# logger_sensors.net
KiCad netlist of a schematic drawn in Altium Designer
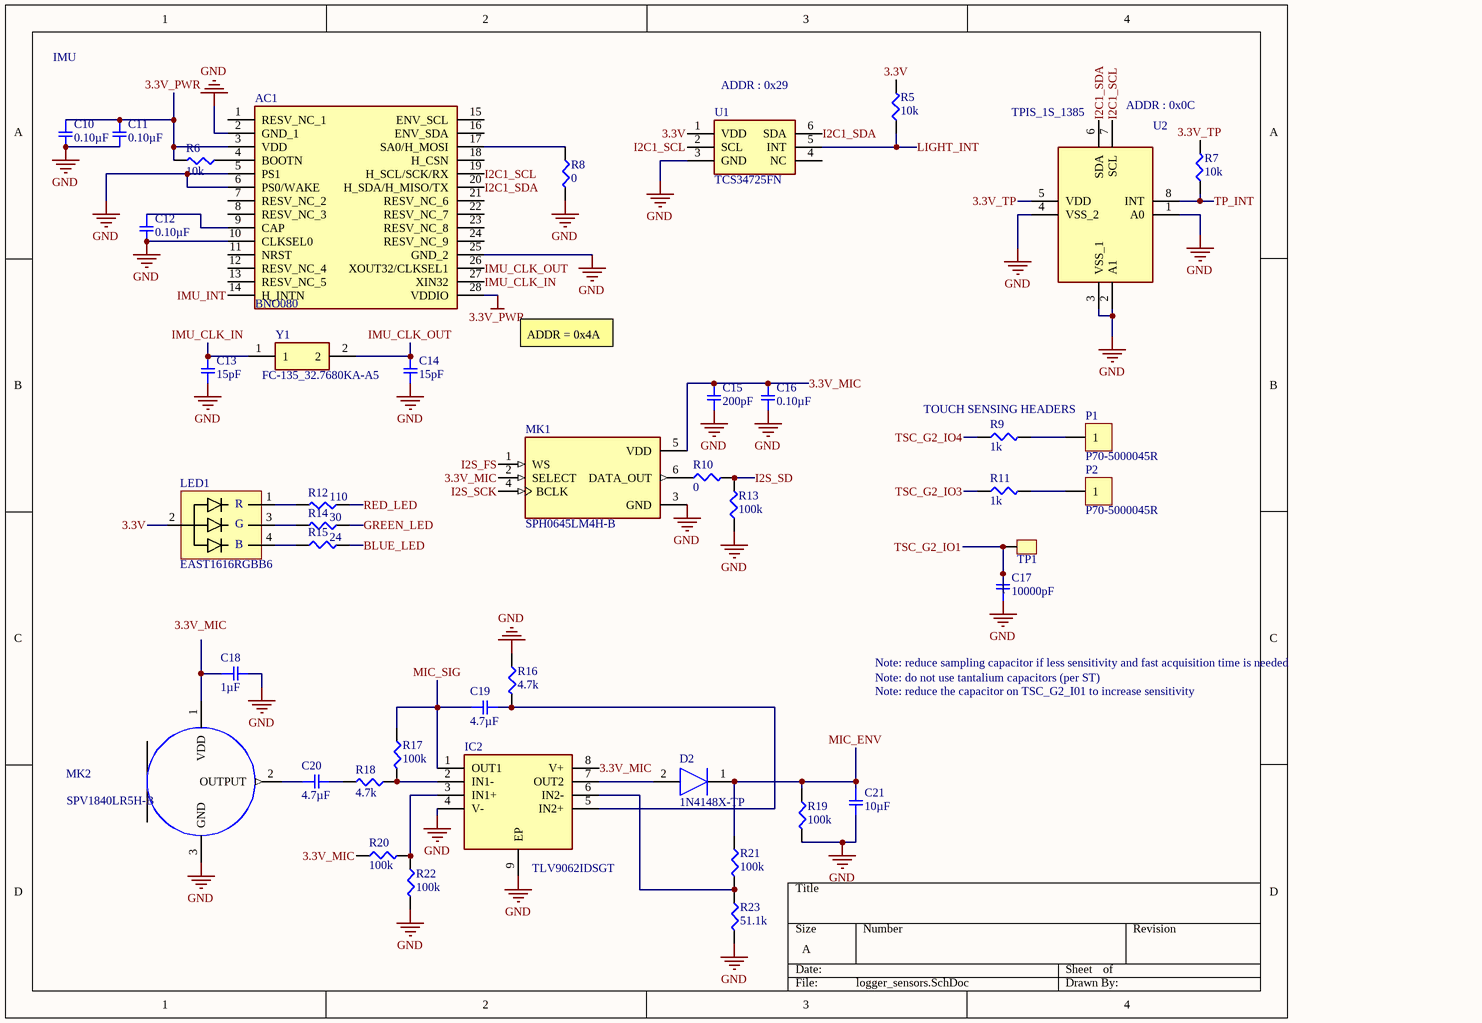
[diagram p0: logger_sensors.SchDoc]

(export (version "E")
  (design (tool "Eeschema 10.0.6"))
  (components
    (comp (ref "AC1")
      (value "BNO080")
      (footprint "BNO080")
      (description "Accelerometer")
      (libsource (lib "*") (part "BNO080"))
    )
    (comp (ref "C10")
      (value "0.10µF")
      (footprint "CAPC1005X55N")
      (description "CAP CER 0.1UF 16V X7R 0402")
      (fields
        (field (name "DIGI-KEY PART NUMBER") "490-4759-1-ND")
        (field (name "PART NUMBER") "GCM155R71C104KA55D")
      )
      (libsource (lib "capacitor_murata_0402") (part "GCM155R71C104KA55D"))
    )
    (comp (ref "C11")
      (value "0.10µF")
      (footprint "CAPC1005X55N")
      (description "CAP CER 0.1UF 16V X7R 0402")
      (fields
        (field (name "DIGI-KEY PART NUMBER") "490-4759-1-ND")
        (field (name "PART NUMBER") "GCM155R71C104KA55D")
      )
      (libsource (lib "capacitor_murata_0402") (part "GCM155R71C104KA55D"))
    )
    (comp (ref "C12")
      (value "0.10µF")
      (footprint "CAPC1005X55N")
      (description "CAP CER 0.1UF 16V X7R 0402")
      (fields
        (field (name "DIGI-KEY PART NUMBER") "490-4759-1-ND")
        (field (name "PART NUMBER") "GCM155R71C104KA55D")
      )
      (libsource (lib "capacitor_murata_0402") (part "GCM155R71C104KA55D"))
    )
    (comp (ref "C13")
      (value "15pF")
      (footprint "CAPC1005X55N")
      (description "CAP CER 15PF 50V NP0 0402")
      (fields
        (field (name "DIGI-KEY PART NUMBER") "490-11147-1-ND")
        (field (name "PART NUMBER") "GCM1555C1H150JA16D")
      )
      (libsource (lib "capacitor_murata_0402") (part "GCM1555C1H150JA16D"))
    )
    (comp (ref "C14")
      (value "15pF")
      (footprint "CAPC1005X55N")
      (description "CAP CER 15PF 50V NP0 0402")
      (fields
        (field (name "DIGI-KEY PART NUMBER") "490-11147-1-ND")
        (field (name "PART NUMBER") "GCM1555C1H150JA16D")
      )
      (libsource (lib "capacitor_murata_0402") (part "GCM1555C1H150JA16D"))
    )
    (comp (ref "C15")
      (value "200pF")
      (footprint "CAPC1005X55N")
      (description "CAP CER 200pF 16V X7R 0402")
      (fields
        (field (name "DIGI-KEY PART NUMBER") "490-4759-1-ND")
        (field (name "PART NUMBER") "GCM155R71C104KA55D")
      )
      (libsource (lib "capacitor_murata_0402") (part "GCM155R71C104KA55D"))
    )
    (comp (ref "C16")
      (value "0.10µF")
      (footprint "CAPC1005X55N")
      (description "CAP CER 0.1UF 16V X7R 0402")
      (fields
        (field (name "DIGI-KEY PART NUMBER") "490-4759-1-ND")
        (field (name "PART NUMBER") "GCM155R71C104KA55D")
      )
      (libsource (lib "capacitor_murata_0402") (part "GCM155R71C104KA55D"))
    )
    (comp (ref "C17")
      (value "10000pF")
      (footprint "SMD-0402C")
      (description "CAP CER 10000PF 50V X7R 0402")
      (fields
        (field (name "DIGI-KEY PART NUMBER") "490-4762-1-ND")
        (field (name "PART NUMBER") "GCM155R71H103KA55D")
      )
      (libsource (lib "capacitor_murata_0402") (part "GCM155R71H103KA55D"))
    )
    (comp (ref "C18")
      (value "1µF")
      (footprint "SMD-0402C")
      (description "CAP CER 1UF 10V X7S 0402")
      (fields
        (field (name "DIGI-KEY PART NUMBER") "490-13409-1-ND")
        (field (name "PART NUMBER") "GCM155C71A105KE38D")
      )
      (libsource (lib "capacitor_murata_0402") (part "GCM155C71A105KE38D"))
    )
    (comp (ref "C19")
      (value "4.7µF")
      (footprint "SMD-0402C")
      (description "CAP CER 4.7UF 6.3V X5R 0402")
      (fields
        (field (name "DIGI-KEY PART NUMBER") "490-5915-1-ND")
        (field (name "PART NUMBER") "GRM155R60J475ME47D")
      )
      (libsource (lib "capacitor_murata_0402") (part "GRM155R60J475ME47D"))
    )
    (comp (ref "C20")
      (value "4.7µF")
      (footprint "SMD-0402C")
      (description "CAP CER 4.7UF 6.3V X5R 0402")
      (fields
        (field (name "DIGI-KEY PART NUMBER") "490-5915-1-ND")
        (field (name "PART NUMBER") "GRM155R60J475ME47D")
      )
      (libsource (lib "capacitor_murata_0402") (part "GRM155R60J475ME47D"))
    )
    (comp (ref "C21")
      (value "10µF")
      (footprint "CAPC1005X55N")
      (description "CAP CER 10UF 16V X7R 0402")
      (fields
        (field (name "DIGI-KEY PART NUMBER") "490-4759-1-ND")
        (field (name "PART NUMBER") "GCM155R71C104KA55D")
      )
      (libsource (lib "capacitor_murata_0402") (part "GCM155R71C104KA55D"))
    )
    (comp (ref "D2")
      (value "1N4148X-TP")
      (footprint "SamacSys:SODFL1608X70N")
      (description "Diode")
      (fields (field (name "MOUSER PART NUMBER") "833-1N4148X-TP"))
      (libsource (lib "*") (part "1N4148X-TP"))
    )
    (comp (ref "IC2")
      (value "TLV9062IDSGT")
      (footprint "SON50P200X200X80-9N")
      (description "Integrated Circuit")
      (fields (field (name "MOUSER PART NUMBER") "595-TLV9062IDSGT"))
      (libsource (lib "SamacSys") (part "TLV9062IDSGT"))
    )
    (comp (ref "LED1")
      (value "EAST1616RGBB6")
      (footprint "EAST1616RGBB6")
      (libsource (lib "schematic_components") (part "EAST1616RGBB6"))
    )
    (comp (ref "MK1")
      (value "SPH0645LM4H-B")
      (footprint "MIC_SPH0645LM4H-B")
      (fields (field (name "DIGI-KEY_PART_NUMBER") "423-1405-1-ND") (field (name "MF") "Knowles"))
      (libsource (lib "schematic_components") (part "SPH0645LM4H-B"))
    )
    (comp (ref "MK2")
      (value "SPV1840LR5H-B")
      (footprint "*MIC_SPV1840LR5H-B")
      (description "Mic Mems Analog")
      (fields (field (name "MF") "Knowles"))
      (libsource (lib "schematic_components") (part "SPV1840LR5H-B"))
    )
    (comp (ref "P1")
      (value "P70-5000045R")
      (footprint "P70-5000045R")
      (libsource (lib "schematic_components") (part "P70-5000045R"))
    )
    (comp (ref "P2")
      (value "P70-5000045R")
      (footprint "P70-5000045R")
      (libsource (lib "schematic_components") (part "P70-5000045R"))
    )
    (comp (ref "R5")
      (value "10k")
      (footprint "SMD-0402-RES")
      (description "RES SMD 10K OHM 5% 1/10W 0402")
      (fields (field (name "PART NUMBER") "ERJ-2GEJ103X") (field (name "DIGI-KEY PART NUMBER") "P10KJCT-ND"))
      (libsource (lib "Panasonic_ERJ_0402") (part "ERJ-2GEJ103X"))
    )
    (comp (ref "R6")
      (value "10k")
      (footprint "SMD-0402-RES")
      (description "RES SMD 10K OHM 5% 1/10W 0402")
      (fields (field (name "PART NUMBER") "ERJ-2GEJ103X") (field (name "DIGI-KEY PART NUMBER") "P10KJCT-ND"))
      (libsource (lib "Panasonic_ERJ_0402") (part "ERJ-2GEJ103X"))
    )
    (comp (ref "R7")
      (value "10k")
      (footprint "SMD-0402-RES")
      (description "RES SMD 10K OHM 5% 1/10W 0402")
      (fields (field (name "PART NUMBER") "ERJ-2GEJ103X") (field (name "DIGI-KEY PART NUMBER") "P10KJCT-ND"))
      (libsource (lib "Panasonic_ERJ_0402") (part "ERJ-2GEJ103X"))
    )
    (comp (ref "R8")
      (value "0")
      (footprint "SMD-0402-RES")
      (description "RES SMD 0K OHM 5% 1/10W 0402")
      (fields (field (name "PART NUMBER") "ERJ-2GEJ103X") (field (name "DIGI-KEY PART NUMBER") "P10KJCT-ND"))
      (libsource (lib "Panasonic_ERJ_0402") (part "ERJ-2GEJ103X"))
    )
    (comp (ref "R9")
      (value "1k")
      (footprint "SMD-0402-RES")
      (description "RES SMD 1K OHM 5% 1/10W 0402")
      (fields (field (name "PART NUMBER") "ERJ-2GEJ102X") (field (name "DIGI-KEY PART NUMBER") "P1.0KJCT-ND"))
      (libsource (lib "Panasonic_ERJ_0402") (part "ERJ-2GEJ102X"))
    )
    (comp (ref "R10")
      (value "0")
      (footprint "SMD-0402-RES")
      (description "RES SMD 0K OHM 5% 1/10W 0402")
      (fields (field (name "PART NUMBER") "ERJ-2GEJ103X") (field (name "DIGI-KEY PART NUMBER") "P10KJCT-ND"))
      (libsource (lib "Panasonic_ERJ_0402") (part "ERJ-2GEJ103X"))
    )
    (comp (ref "R11")
      (value "1k")
      (footprint "SMD-0402-RES")
      (description "RES SMD 1K OHM 5% 1/10W 0402")
      (fields (field (name "PART NUMBER") "ERJ-2GEJ102X") (field (name "DIGI-KEY PART NUMBER") "P1.0KJCT-ND"))
      (libsource (lib "Panasonic_ERJ_0402") (part "ERJ-2GEJ102X"))
    )
    (comp (ref "R12")
      (value "110")
      (footprint "SMD-0402-RES")
      (description "RES SMD 110 OHM 5% 1/10W 0402")
      (fields (field (name "PART NUMBER") "ERJ-2GEJ103X") (field (name "DIGI-KEY PART NUMBER") "P10KJCT-ND"))
      (libsource (lib "Panasonic_ERJ_0402") (part "ERJ-2GEJ103X"))
    )
    (comp (ref "R13")
      (value "100k")
      (footprint "SMD-0402-RES")
      (description "RES SMD 100K OHM 5% 1/10W 0402")
      (fields (field (name "PART NUMBER") "ERJ-2GEJ103X") (field (name "DIGI-KEY PART NUMBER") "P10KJCT-ND"))
      (libsource (lib "Panasonic_ERJ_0402") (part "ERJ-2GEJ103X"))
    )
    (comp (ref "R14")
      (value "30")
      (footprint "SMD-0402-RES")
      (description "RES SMD 110 OHM 5% 1/10W 0402")
      (fields (field (name "PART NUMBER") "ERJ-2GEJ103X") (field (name "DIGI-KEY PART NUMBER") "P10KJCT-ND"))
      (libsource (lib "Panasonic_ERJ_0402") (part "ERJ-2GEJ103X"))
    )
    (comp (ref "R15")
      (value "24")
      (footprint "SMD-0402-RES")
      (description "RES SMD 110 OHM 5% 1/10W 0402")
      (fields (field (name "PART NUMBER") "ERJ-2GEJ103X") (field (name "DIGI-KEY PART NUMBER") "P10KJCT-ND"))
      (libsource (lib "Panasonic_ERJ_0402") (part "ERJ-2GEJ103X"))
    )
    (comp (ref "R16")
      (value "4.7k")
      (footprint "SMD-0402-RES")
      (description "RES SMD 4.7K OHM 5% 1/10W 0402")
      (fields (field (name "PART NUMBER") "ERJ-2GEJ103X") (field (name "DIGI-KEY PART NUMBER") "P10KJCT-ND"))
      (libsource (lib "Panasonic_ERJ_0402") (part "ERJ-2GEJ103X"))
    )
    (comp (ref "R17")
      (value "100k")
      (footprint "SMD-0402-RES")
      (description "RES SMD 100K OHM 5% 1/10W 0402")
      (fields (field (name "PART NUMBER") "ERJ-2GEJ103X") (field (name "DIGI-KEY PART NUMBER") "P10KJCT-ND"))
      (libsource (lib "Panasonic_ERJ_0402") (part "ERJ-2GEJ103X"))
    )
    (comp (ref "R18")
      (value "4.7k")
      (footprint "SMD-0402-RES")
      (description "RES SMD 4.7K OHM 5% 1/10W 0402")
      (fields (field (name "PART NUMBER") "ERJ-2GEJ103X") (field (name "DIGI-KEY PART NUMBER") "P10KJCT-ND"))
      (libsource (lib "Panasonic_ERJ_0402") (part "ERJ-2GEJ103X"))
    )
    (comp (ref "R19")
      (value "100k")
      (footprint "SMD-0402-RES")
      (description "RES SMD 100K OHM 5% 1/10W 0402")
      (fields (field (name "PART NUMBER") "ERJ-2GEJ103X") (field (name "DIGI-KEY PART NUMBER") "P10KJCT-ND"))
      (libsource (lib "Panasonic_ERJ_0402") (part "ERJ-2GEJ103X"))
    )
    (comp (ref "R20")
      (value "100k")
      (footprint "SMD-0402-RES")
      (description "RES SMD 100K OHM 5% 1/10W 0402")
      (fields (field (name "PART NUMBER") "ERJ-2GEJ103X") (field (name "DIGI-KEY PART NUMBER") "P10KJCT-ND"))
      (libsource (lib "Panasonic_ERJ_0402") (part "ERJ-2GEJ103X"))
    )
    (comp (ref "R21")
      (value "100k")
      (footprint "SMD-0402-RES")
      (description "RES SMD 100K OHM 5% 1/10W 0402")
      (fields (field (name "PART NUMBER") "ERJ-2GEJ103X") (field (name "DIGI-KEY PART NUMBER") "P10KJCT-ND"))
      (libsource (lib "Panasonic_ERJ_0402") (part "ERJ-2GEJ103X"))
    )
    (comp (ref "R22")
      (value "100k")
      (footprint "SMD-0402-RES")
      (description "RES SMD 100K OHM 5% 1/10W 0402")
      (fields (field (name "PART NUMBER") "ERJ-2GEJ103X") (field (name "DIGI-KEY PART NUMBER") "P10KJCT-ND"))
      (libsource (lib "Panasonic_ERJ_0402") (part "ERJ-2GEJ103X"))
    )
    (comp (ref "R23")
      (value "51.1k")
      (footprint "SMD-0402-RES")
      (description "RES SMD 51.1K OHM 5% 1/10W 0402")
      (fields (field (name "PART NUMBER") "ERJ-2GEJ103X") (field (name "DIGI-KEY PART NUMBER") "P10KJCT-ND"))
      (libsource (lib "Panasonic_ERJ_0402") (part "ERJ-2GEJ103X"))
    )
    (comp (ref "TP1")
      (value "TestPoint")
      (footprint "TestPoint_0.4mm")
      (libsource (lib "schematic_components") (part "TestPoint"))
    )
    (comp (ref "U1")
      (value "TCS34725FN")
      (footprint "SamacSys:FN_1")
      (description "Undefined or Miscellaneous")
      (fields (field (name "MOUSER PART NUMBER") "985-TCS34725FN") (field (name "RS PART NUMBER") "1024173P"))
      (libsource (lib "*") (part "TCS34725FN"))
    )
    (comp (ref "U2")
      (value "TPIS_1S_1385")
      (footprint "SamacSys:TPIS_1S_1385")
      (description "Undefined or Miscellaneous")
      (fields (field (name "MANUFACTURER_PART_NUMBER") "TPIS 1S 1385"))
      (libsource (lib "*") (part "TPIS_1S_1385"))
    )
    (comp (ref "Y1")
      (value "FC-135_32.7680KA-A5")
      (footprint "FC135327680KAAG0")
      (description "Crystal or Oscillator")
      (fields
        (field (name "MANUFACTURER_PART_NUMBER") "FC-135 32.7680KA-A5")
        (field (name "MOUSER PART NUMBER") "732-FC135-32.76KAA3")
      )
      (libsource (lib "*") (part "FC-135_32.7680KA-A3"))
    )
  )
  (nets
    (net (code "1") (name "/3.3V") (class "Default")
      (node (ref "LED1") (pin "2") (pinfunction "2_2") (pintype "passive"))
      (node (ref "R5") (pin "2") (pinfunction "2_2") (pintype "passive"))
      (node (ref "U1") (pin "1") (pinfunction "VDD_1") (pintype "passive"))
    )
    (net (code "2") (name "/3.3V_MIC") (class "Default")
      (node (ref "C15") (pin "1") (pinfunction "1_1") (pintype "passive"))
      (node (ref "C16") (pin "1") (pinfunction "1_1") (pintype "passive"))
      (node (ref "IC2") (pin "8") (pinfunction "V+_8") (pintype "passive"))
      (node (ref "MK1") (pin "2") (pinfunction "SELECT_2") (pintype "input"))
      (node (ref "MK1") (pin "5") (pinfunction "VDD_5") (pintype "power_in"))
      (node (ref "R20") (pin "1") (pinfunction "1_1") (pintype "passive"))
    )
    (net (code "3") (name "/3.3V_TP") (class "Default")
      (node (ref "R7") (pin "2") (pinfunction "2_2") (pintype "passive"))
      (node (ref "U2") (pin "5") (pinfunction "VDD_5") (pintype "passive"))
    )
    (net (code "4") (name "/BLUE_LED") (class "Default")
      (node (ref "R15") (pin "2") (pinfunction "2_2") (pintype "passive"))
    )
    (net (code "5") (name "/GREEN_LED") (class "Default")
      (node (ref "R14") (pin "1") (pinfunction "1_1") (pintype "passive"))
    )
    (net (code "6") (name "/I2C1_SCL") (class "Default")
      (node (ref "AC1") (pin "19") (pinfunction "H_SCL/SCK/RX_19") (pintype "passive"))
      (node (ref "U1") (pin "2") (pinfunction "SCL_2") (pintype "passive"))
      (node (ref "U2") (pin "7") (pinfunction "SCL_7") (pintype "passive"))
    )
    (net (code "7") (name "/I2C1_SDA") (class "Default")
      (node (ref "AC1") (pin "20") (pinfunction "H_SDA/H_MISO/TX_20") (pintype "passive"))
      (node (ref "U1") (pin "6") (pinfunction "SDA_6") (pintype "passive"))
      (node (ref "U2") (pin "6") (pinfunction "SDA_6") (pintype "passive"))
    )
    (net (code "8") (name "/I2S_FS") (class "Default")
      (node (ref "MK1") (pin "1") (pinfunction "WS_1") (pintype "input"))
    )
    (net (code "9") (name "/I2S_SCK") (class "Default")
      (node (ref "MK1") (pin "4") (pinfunction "BCLK_4") (pintype "input"))
    )
    (net (code "10") (name "/I2S_SD") (class "Default")
      (node (ref "R10") (pin "2") (pinfunction "2_2") (pintype "passive"))
      (node (ref "R13") (pin "2") (pinfunction "2_2") (pintype "passive"))
    )
    (net (code "11") (name "/IMU_CLK_IN") (class "Default")
      (node (ref "AC1") (pin "27") (pinfunction "XIN32_27") (pintype "passive"))
      (node (ref "C13") (pin "1") (pinfunction "1_1") (pintype "passive"))
      (node (ref "Y1") (pin "1") (pinfunction "1_1") (pintype "passive"))
    )
    (net (code "12") (name "/IMU_CLK_OUT") (class "Default")
      (node (ref "AC1") (pin "26") (pinfunction "XOUT32/CLKSEL1_26") (pintype "passive"))
      (node (ref "C14") (pin "1") (pinfunction "1_1") (pintype "passive"))
      (node (ref "Y1") (pin "2") (pinfunction "2_2") (pintype "passive"))
    )
    (net (code "13") (name "/IMU_INT") (class "Default")
      (node (ref "AC1") (pin "14") (pinfunction "H_INTN_14") (pintype "passive"))
    )
    (net (code "14") (name "/LIGHT_INT") (class "Default")
      (node (ref "R5") (pin "1") (pinfunction "1_1") (pintype "passive"))
      (node (ref "U1") (pin "5") (pinfunction "INT_5") (pintype "passive"))
    )
    (net (code "15") (name "/MIC_ENV") (class "Default")
      (node (ref "C21") (pin "1") (pinfunction "1_1") (pintype "passive"))
      (node (ref "D2") (pin "1") (pinfunction "K_1") (pintype "passive"))
      (node (ref "R19") (pin "1") (pinfunction "1_1") (pintype "passive"))
      (node (ref "R21") (pin "1") (pinfunction "1_1") (pintype "passive"))
    )
    (net (code "16") (name "/MIC_SIG") (class "Default")
      (node (ref "C19") (pin "1") (pinfunction "1_1") (pintype "passive"))
      (node (ref "IC2") (pin "1") (pinfunction "OUT1_1") (pintype "passive"))
      (node (ref "R17") (pin "1") (pinfunction "1_1") (pintype "passive"))
    )
    (net (code "17") (name "/RED_LED") (class "Default")
      (node (ref "R12") (pin "1") (pinfunction "1_1") (pintype "passive"))
    )
    (net (code "18") (name "/TP_INT") (class "Default")
      (node (ref "R7") (pin "1") (pinfunction "1_1") (pintype "passive"))
      (node (ref "U2") (pin "8") (pinfunction "INT_8") (pintype "passive"))
    )
    (net (code "19") (name "/TSC_G2_IO1") (class "Default")
      (node (ref "C17") (pin "2") (pinfunction "2_2") (pintype "passive"))
      (node (ref "TP1") (pin "1") (pinfunction "1_1") (pintype "passive"))
    )
    (net (code "20") (name "/TSC_G2_IO3") (class "Default")
      (node (ref "R11") (pin "1") (pinfunction "1_1") (pintype "passive"))
    )
    (net (code "21") (name "/TSC_G2_IO4") (class "Default")
      (node (ref "R9") (pin "1") (pinfunction "1_1") (pintype "passive"))
    )
    (net (code "22") (name "3.3V_PWR") (class "Default")
      (node (ref "AC1") (pin "28") (pinfunction "VDDIO_28") (pintype "passive"))
      (node (ref "AC1") (pin "3") (pinfunction "VDD_3") (pintype "passive"))
      (node (ref "C10") (pin "1") (pinfunction "1_1") (pintype "passive"))
      (node (ref "C11") (pin "1") (pinfunction "1_1") (pintype "passive"))
      (node (ref "R6") (pin "2") (pinfunction "2_2") (pintype "passive"))
    )
    (net (code "23") (name "GND") (class "Default")
      (node (ref "AC1") (pin "10") (pinfunction "CLKSEL0_10") (pintype "passive"))
      (node (ref "AC1") (pin "2") (pinfunction "GND_1_2") (pintype "passive"))
      (node (ref "AC1") (pin "25") (pinfunction "GND_2_25") (pintype "passive"))
      (node (ref "AC1") (pin "5") (pinfunction "PS1_5") (pintype "passive"))
      (node (ref "AC1") (pin "6") (pinfunction "PS0/WAKE_6") (pintype "passive"))
      (node (ref "C10") (pin "2") (pinfunction "2_2") (pintype "passive"))
      (node (ref "C11") (pin "2") (pinfunction "2_2") (pintype "passive"))
      (node (ref "C12") (pin "2") (pinfunction "2_2") (pintype "passive"))
      (node (ref "C13") (pin "2") (pinfunction "2_2") (pintype "passive"))
      (node (ref "C14") (pin "2") (pinfunction "2_2") (pintype "passive"))
      (node (ref "C15") (pin "2") (pinfunction "2_2") (pintype "passive"))
      (node (ref "C16") (pin "2") (pinfunction "2_2") (pintype "passive"))
      (node (ref "C17") (pin "1") (pinfunction "1_1") (pintype "passive"))
      (node (ref "C18") (pin "2") (pinfunction "2_2") (pintype "passive"))
      (node (ref "C21") (pin "2") (pinfunction "2_2") (pintype "passive"))
      (node (ref "IC2") (pin "4") (pinfunction "V-_4") (pintype "passive"))
      (node (ref "IC2") (pin "9") (pinfunction "EP_9") (pintype "passive"))
      (node (ref "MK1") (pin "3") (pinfunction "GND_3") (pintype "power_in"))
      (node (ref "MK2") (pin "3") (pinfunction "GND_3") (pintype "passive"))
      (node (ref "R13") (pin "1") (pinfunction "1_1") (pintype "passive"))
      (node (ref "R16") (pin "1") (pinfunction "1_1") (pintype "passive"))
      (node (ref "R19") (pin "2") (pinfunction "2_2") (pintype "passive"))
      (node (ref "R22") (pin "2") (pinfunction "2_2") (pintype "passive"))
      (node (ref "R23") (pin "2") (pinfunction "2_2") (pintype "passive"))
      (node (ref "R8") (pin "2") (pinfunction "2_2") (pintype "passive"))
      (node (ref "U1") (pin "3") (pinfunction "GND_3") (pintype "passive"))
      (node (ref "U2") (pin "1") (pinfunction "A0_1") (pintype "passive"))
      (node (ref "U2") (pin "2") (pinfunction "A1_2") (pintype "passive"))
      (node (ref "U2") (pin "3") (pinfunction "VSS_1_3") (pintype "passive"))
      (node (ref "U2") (pin "4") (pinfunction "VSS_2_4") (pintype "passive"))
    )
    (net (code "24") (name "Net-(AC1-BOOTN)") (class "Default")
      (node (ref "AC1") (pin "4") (pinfunction "BOOTN_4") (pintype "passive"))
      (node (ref "R6") (pin "1") (pinfunction "1_1") (pintype "passive"))
    )
    (net (code "25") (name "Net-(AC1-CAP)") (class "Default")
      (node (ref "AC1") (pin "9") (pinfunction "CAP_9") (pintype "passive"))
      (node (ref "C12") (pin "1") (pinfunction "1_1") (pintype "passive"))
    )
    (net (code "26") (name "Net-(AC1-SA0{slash}H_MOSI)") (class "Default")
      (node (ref "AC1") (pin "17") (pinfunction "SA0/H_MOSI_17") (pintype "passive"))
      (node (ref "R8") (pin "1") (pinfunction "1_1") (pintype "passive"))
    )
    (net (code "27") (name "Net-(C20-Pad2)") (class "Default")
      (node (ref "C20") (pin "2") (pinfunction "2_2") (pintype "passive"))
      (node (ref "R18") (pin "2") (pinfunction "2_2") (pintype "passive"))
    )
    (net (code "28") (name "Net-(D2-A)") (class "Default")
      (node (ref "D2") (pin "2") (pinfunction "A_2") (pintype "passive"))
      (node (ref "IC2") (pin "7") (pinfunction "OUT2_7") (pintype "passive"))
    )
    (net (code "29") (name "Net-(IC2-IN1+)") (class "Default")
      (node (ref "IC2") (pin "3") (pinfunction "IN1+_3") (pintype "passive"))
      (node (ref "R20") (pin "2") (pinfunction "2_2") (pintype "passive"))
      (node (ref "R22") (pin "1") (pinfunction "1_1") (pintype "passive"))
    )
    (net (code "30") (name "Net-(IC2-IN1-)") (class "Default")
      (node (ref "IC2") (pin "2") (pinfunction "IN1-_2") (pintype "passive"))
      (node (ref "R17") (pin "2") (pinfunction "2_2") (pintype "passive"))
      (node (ref "R18") (pin "1") (pinfunction "1_1") (pintype "passive"))
    )
    (net (code "31") (name "Net-(IC2-IN2+)") (class "Default")
      (node (ref "C19") (pin "2") (pinfunction "2_2") (pintype "passive"))
      (node (ref "IC2") (pin "5") (pinfunction "IN2+_5") (pintype "passive"))
      (node (ref "R16") (pin "2") (pinfunction "2_2") (pintype "passive"))
    )
    (net (code "32") (name "Net-(IC2-IN2-)") (class "Default")
      (node (ref "IC2") (pin "6") (pinfunction "IN2-_6") (pintype "passive"))
      (node (ref "R21") (pin "2") (pinfunction "2_2") (pintype "passive"))
      (node (ref "R23") (pin "1") (pinfunction "1_1") (pintype "passive"))
    )
    (net (code "33") (name "Net-(LED1-Pad1)") (class "Default")
      (node (ref "LED1") (pin "1") (pinfunction "1_1") (pintype "passive"))
      (node (ref "R12") (pin "2") (pinfunction "2_2") (pintype "passive"))
    )
    (net (code "34") (name "Net-(LED1-Pad3)") (class "Default")
      (node (ref "LED1") (pin "3") (pinfunction "3_3") (pintype "passive"))
      (node (ref "R14") (pin "2") (pinfunction "2_2") (pintype "passive"))
    )
    (net (code "35") (name "Net-(LED1-Pad4)") (class "Default")
      (node (ref "LED1") (pin "4") (pinfunction "4_4") (pintype "passive"))
      (node (ref "R15") (pin "1") (pinfunction "1_1") (pintype "passive"))
    )
    (net (code "36") (name "Net-(MK2-OUTPUT)") (class "Default")
      (node (ref "C20") (pin "1") (pinfunction "1_1") (pintype "passive"))
      (node (ref "MK2") (pin "2") (pinfunction "OUTPUT_2") (pintype "output"))
    )
    (net (code "37") (name "Net-(MK2-VDD)") (class "Default")
      (node (ref "C18") (pin "1") (pinfunction "1_1") (pintype "passive"))
      (node (ref "MK2") (pin "1") (pinfunction "VDD_1") (pintype "power_in"))
    )
    (net (code "38") (name "Net-(P1-Pad1)") (class "Default")
      (node (ref "P1") (pin "1") (pinfunction "1_1") (pintype "passive"))
      (node (ref "R9") (pin "2") (pinfunction "2_2") (pintype "passive"))
    )
    (net (code "39") (name "Net-(P2-Pad1)") (class "Default")
      (node (ref "P2") (pin "1") (pinfunction "1_1") (pintype "passive"))
      (node (ref "R11") (pin "2") (pinfunction "2_2") (pintype "passive"))
    )
    (net (code "40") (name "unconnected-(AC1-ENV_SCL-Pad15)") (class "Default")
      (node (ref "AC1") (pin "15") (pinfunction "ENV_SCL_15") (pintype "passive"))
    )
    (net (code "41") (name "unconnected-(AC1-ENV_SDA-Pad16)") (class "Default")
      (node (ref "AC1") (pin "16") (pinfunction "ENV_SDA_16") (pintype "passive"))
    )
    (net (code "42") (name "unconnected-(AC1-H_CSN-Pad18)") (class "Default")
      (node (ref "AC1") (pin "18") (pinfunction "H_CSN_18") (pintype "passive"))
    )
    (net (code "43") (name "unconnected-(AC1-NRST-Pad11)") (class "Default")
      (node (ref "AC1") (pin "11") (pinfunction "NRST_11") (pintype "passive"))
    )
    (net (code "44") (name "unconnected-(AC1-RESV_NC_1-Pad1)") (class "Default")
      (node (ref "AC1") (pin "1") (pinfunction "RESV_NC_1_1") (pintype "passive"))
    )
    (net (code "45") (name "unconnected-(AC1-RESV_NC_2-Pad7)") (class "Default")
      (node (ref "AC1") (pin "7") (pinfunction "RESV_NC_2_7") (pintype "passive"))
    )
    (net (code "46") (name "unconnected-(AC1-RESV_NC_3-Pad8)") (class "Default")
      (node (ref "AC1") (pin "8") (pinfunction "RESV_NC_3_8") (pintype "passive"))
    )
    (net (code "47") (name "unconnected-(AC1-RESV_NC_4-Pad12)") (class "Default")
      (node (ref "AC1") (pin "12") (pinfunction "RESV_NC_4_12") (pintype "passive"))
    )
    (net (code "48") (name "unconnected-(AC1-RESV_NC_5-Pad13)") (class "Default")
      (node (ref "AC1") (pin "13") (pinfunction "RESV_NC_5_13") (pintype "passive"))
    )
    (net (code "49") (name "unconnected-(AC1-RESV_NC_6-Pad21)") (class "Default")
      (node (ref "AC1") (pin "21") (pinfunction "RESV_NC_6_21") (pintype "passive"))
    )
    (net (code "50") (name "unconnected-(AC1-RESV_NC_7-Pad22)") (class "Default")
      (node (ref "AC1") (pin "22") (pinfunction "RESV_NC_7_22") (pintype "passive"))
    )
    (net (code "51") (name "unconnected-(AC1-RESV_NC_8-Pad23)") (class "Default")
      (node (ref "AC1") (pin "23") (pinfunction "RESV_NC_8_23") (pintype "passive"))
    )
    (net (code "52") (name "unconnected-(AC1-RESV_NC_9-Pad24)") (class "Default")
      (node (ref "AC1") (pin "24") (pinfunction "RESV_NC_9_24") (pintype "passive"))
    )
    (net (code "53") (name "unconnected-(MK1-DATA_OUT-Pad6)") (class "Default")
      (node (ref "MK1") (pin "6") (pinfunction "DATA_OUT_6") (pintype "output"))
    )
    (net (code "54") (name "unconnected-(R10-Pad1)") (class "Default")
      (node (ref "R10") (pin "1") (pinfunction "1_1") (pintype "passive"))
    )
    (net (code "55") (name "unconnected-(U1-NC-Pad4)") (class "Default")
      (node (ref "U1") (pin "4") (pinfunction "NC_4") (pintype "passive"))
    )
  )
)
